# 2022_LEDs.net
KiCad netlist of a schematic drawn in EAGLE
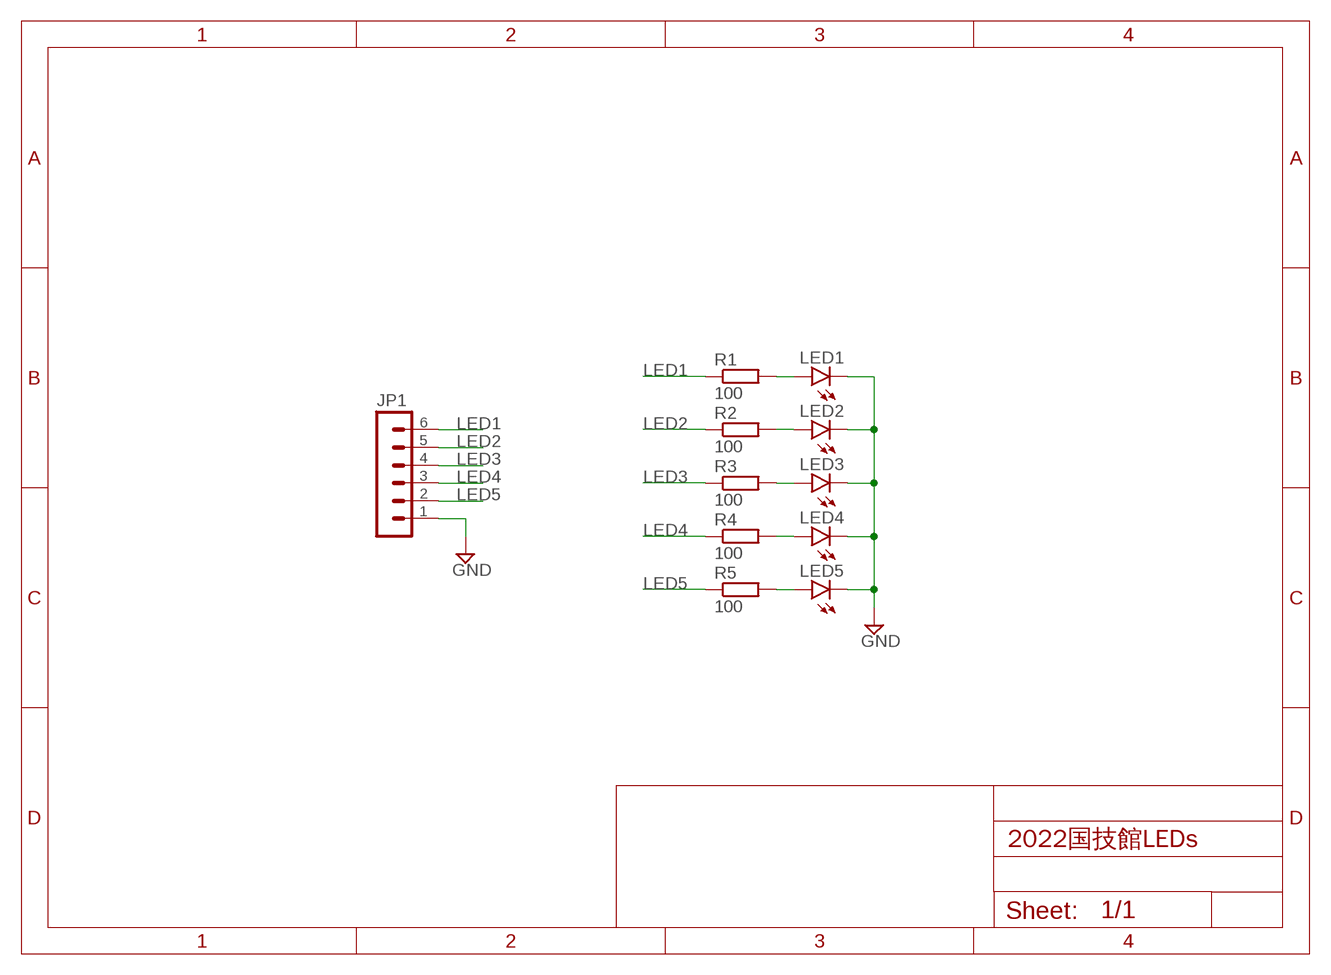
[diagram p0: schematic, sheet 1]

(export (version "E")
  (design (tool "Eeschema 10.0.6"))
  (components
    (comp (ref "JP1")
      (value "06-JST")
      (footprint "eagle-import:B6B-XH")
      (libsource (lib "eagle-import") (part "06-JST"))
    )
    (comp (ref "LED1")
      (value "LED5MM")
      (footprint "eagle-import:LED5MM")
      (libsource (lib "eagle-import") (part "LED5MM"))
    )
    (comp (ref "LED2")
      (value "LED5MM")
      (footprint "eagle-import:LED5MM")
      (libsource (lib "eagle-import") (part "LED5MM"))
    )
    (comp (ref "LED3")
      (value "LED5MM")
      (footprint "eagle-import:LED5MM")
      (libsource (lib "eagle-import") (part "LED5MM"))
    )
    (comp (ref "LED4")
      (value "LED5MM")
      (footprint "eagle-import:LED5MM")
      (libsource (lib "eagle-import") (part "LED5MM"))
    )
    (comp (ref "LED5")
      (value "LED5MM")
      (footprint "eagle-import:LED5MM")
      (libsource (lib "eagle-import") (part "LED5MM"))
    )
    (comp (ref "R1")
      (value "100")
      (footprint "eagle-import:0204_7")
      (libsource (lib "eagle-import") (part "R-EU_0204/7"))
    )
    (comp (ref "R2")
      (value "100")
      (footprint "eagle-import:0204_7")
      (libsource (lib "eagle-import") (part "R-EU_0204/7"))
    )
    (comp (ref "R3")
      (value "100")
      (footprint "eagle-import:0204_7")
      (libsource (lib "eagle-import") (part "R-EU_0204/7"))
    )
    (comp (ref "R4")
      (value "100")
      (footprint "eagle-import:0204_7")
      (libsource (lib "eagle-import") (part "R-EU_0204/7"))
    )
    (comp (ref "R5")
      (value "100")
      (footprint "eagle-import:0204_7")
      (libsource (lib "eagle-import") (part "R-EU_0204/7"))
    )
  )
  (nets
    (net (code "1") (name "/LED1") (class "Default")
      (node (ref "JP1") (pin "6") (pinfunction "6_6") (pintype "passive"))
      (node (ref "R1") (pin "1") (pinfunction "1_1") (pintype "passive"))
    )
    (net (code "2") (name "/LED2") (class "Default")
      (node (ref "JP1") (pin "5") (pinfunction "5_5") (pintype "passive"))
      (node (ref "R2") (pin "1") (pinfunction "1_1") (pintype "passive"))
    )
    (net (code "3") (name "/LED3") (class "Default")
      (node (ref "JP1") (pin "4") (pinfunction "4_4") (pintype "passive"))
      (node (ref "R3") (pin "1") (pinfunction "1_1") (pintype "passive"))
    )
    (net (code "4") (name "/LED4") (class "Default")
      (node (ref "JP1") (pin "3") (pinfunction "3_3") (pintype "passive"))
      (node (ref "R4") (pin "1") (pinfunction "1_1") (pintype "passive"))
    )
    (net (code "5") (name "/LED5") (class "Default")
      (node (ref "JP1") (pin "2") (pinfunction "2_2") (pintype "passive"))
      (node (ref "R5") (pin "1") (pinfunction "1_1") (pintype "passive"))
    )
    (net (code "6") (name "GND") (class "Default")
      (node (ref "JP1") (pin "1") (pinfunction "1_1") (pintype "passive"))
      (node (ref "LED1") (pin "K") (pinfunction "C_K") (pintype "passive"))
      (node (ref "LED2") (pin "K") (pinfunction "C_K") (pintype "passive"))
      (node (ref "LED3") (pin "K") (pinfunction "C_K") (pintype "passive"))
      (node (ref "LED4") (pin "K") (pinfunction "C_K") (pintype "passive"))
      (node (ref "LED5") (pin "K") (pinfunction "C_K") (pintype "passive"))
    )
    (net (code "7") (name "Net-(LED1-PadA)") (class "Default")
      (node (ref "LED1") (pin "A") (pinfunction "A_A") (pintype "passive"))
      (node (ref "R1") (pin "2") (pinfunction "2_2") (pintype "passive"))
    )
    (net (code "8") (name "Net-(LED2-PadA)") (class "Default")
      (node (ref "LED2") (pin "A") (pinfunction "A_A") (pintype "passive"))
      (node (ref "R2") (pin "2") (pinfunction "2_2") (pintype "passive"))
    )
    (net (code "9") (name "Net-(LED3-PadA)") (class "Default")
      (node (ref "LED3") (pin "A") (pinfunction "A_A") (pintype "passive"))
      (node (ref "R3") (pin "2") (pinfunction "2_2") (pintype "passive"))
    )
    (net (code "10") (name "Net-(LED4-PadA)") (class "Default")
      (node (ref "LED4") (pin "A") (pinfunction "A_A") (pintype "passive"))
      (node (ref "R4") (pin "2") (pinfunction "2_2") (pintype "passive"))
    )
    (net (code "11") (name "Net-(LED5-PadA)") (class "Default")
      (node (ref "LED5") (pin "A") (pinfunction "A_A") (pintype "passive"))
      (node (ref "R5") (pin "2") (pinfunction "2_2") (pintype "passive"))
    )
  )
)
